# devboard.net
KiCad netlist of a schematic drawn in EAGLE
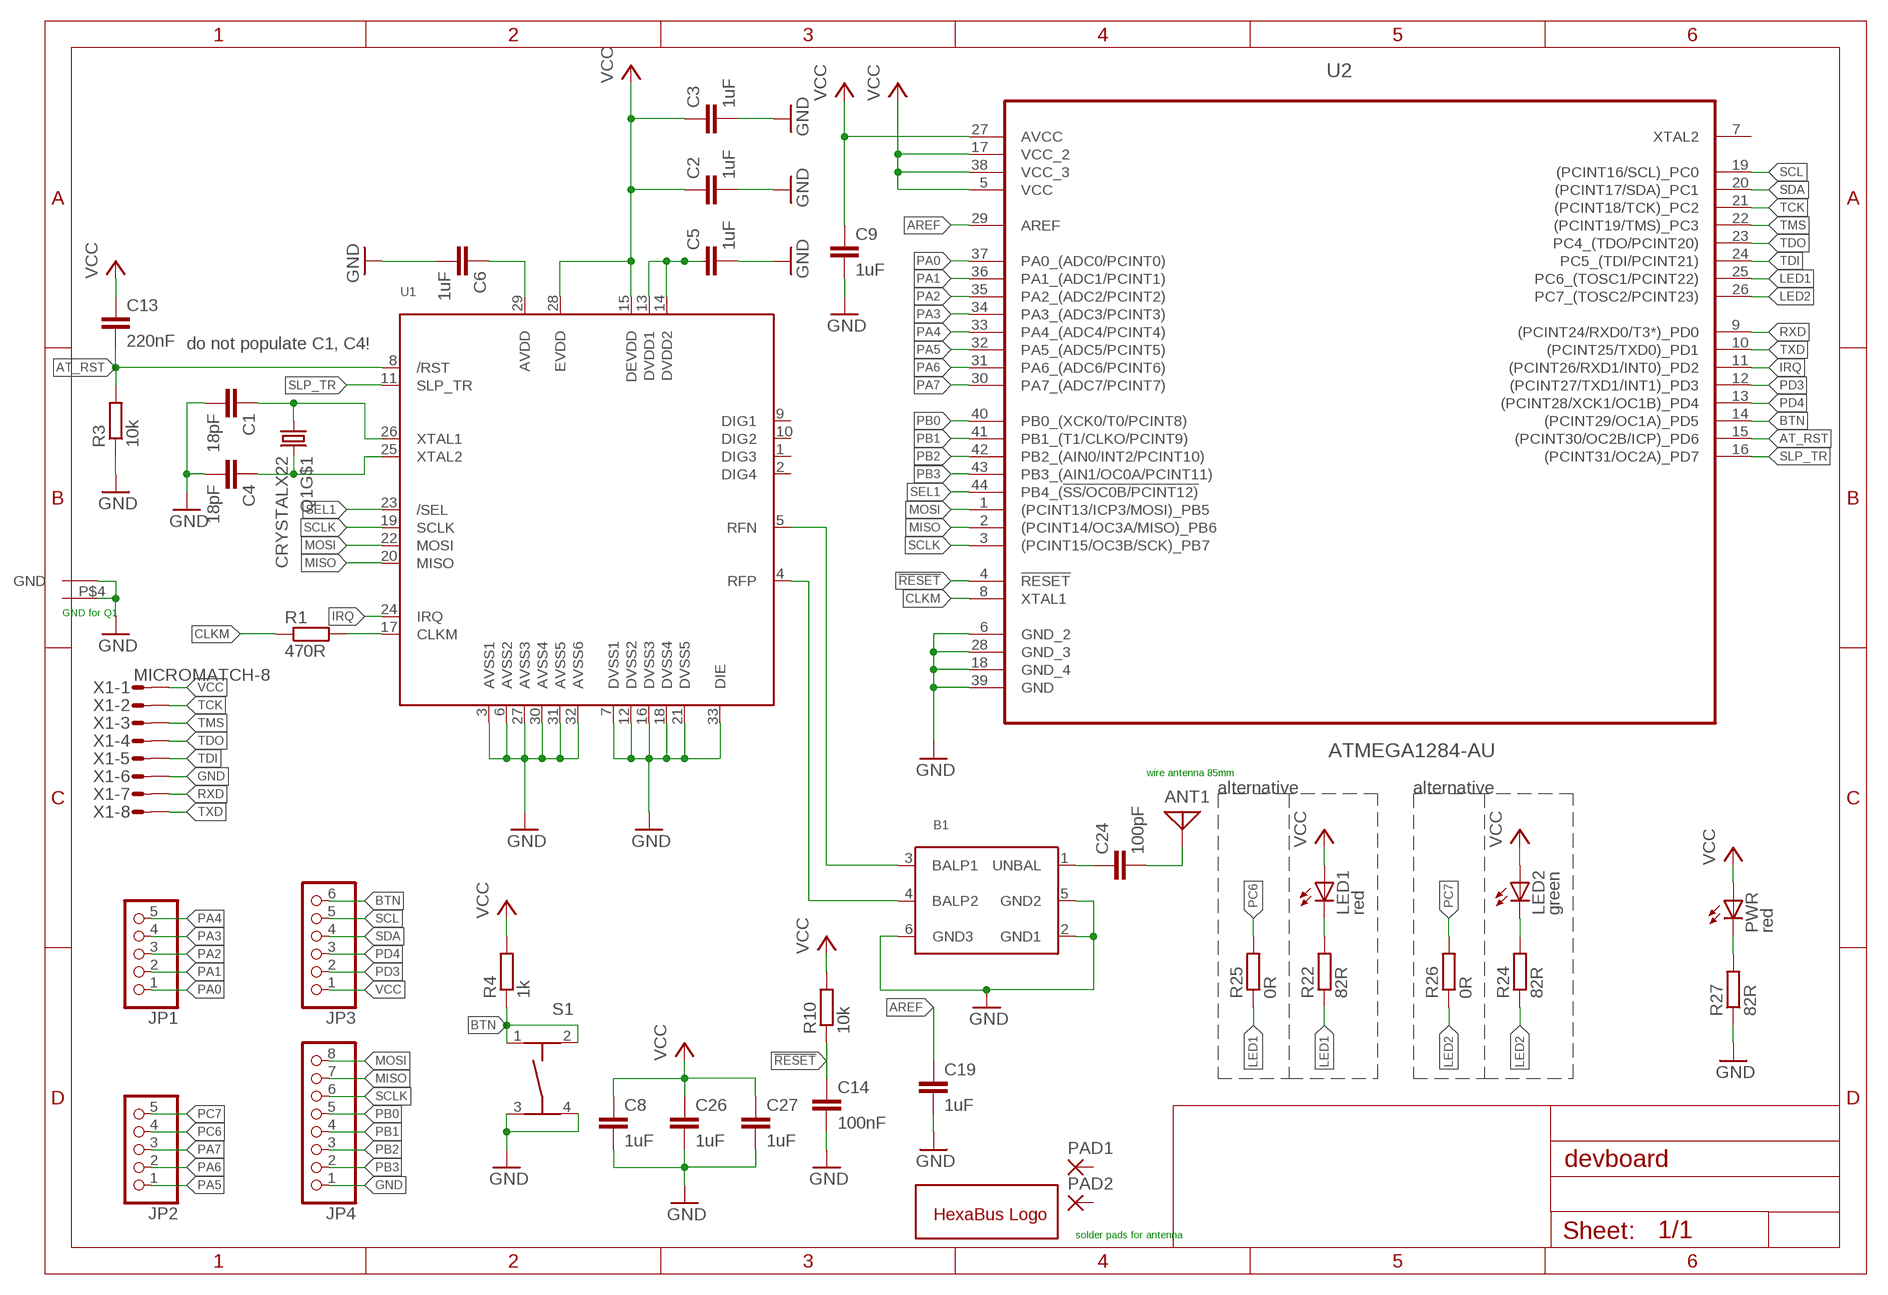
[diagram p0: schematic, sheet 1]

(export (version "E")
  (design (tool "Eeschema 10.0.6"))
  (components
    (comp (ref "ANT1")
      (value "ANTENNA")
      (footprint "eagle-import:PAD-01")
      (libsource (lib "eagle-import") (part "ANTENNA"))
    )
    (comp (ref "B1")
      (value "BALUN+LP")
      (footprint "eagle-import:BALUN0805")
      (libsource (lib "eagle-import") (part "BALUN+LP"))
    )
    (comp (ref "C1")
      (value "18pF")
      (footprint "eagle-import:C0603")
      (libsource (lib "eagle-import") (part "C-EUC0603"))
    )
    (comp (ref "C2")
      (value "1uF")
      (footprint "eagle-import:C0603")
      (libsource (lib "eagle-import") (part "C-EUC0603"))
    )
    (comp (ref "C3")
      (value "1uF")
      (footprint "eagle-import:C0603")
      (libsource (lib "eagle-import") (part "C-EUC0603"))
    )
    (comp (ref "C4")
      (value "18pF")
      (footprint "eagle-import:C0603")
      (libsource (lib "eagle-import") (part "C-EUC0603"))
    )
    (comp (ref "C5")
      (value "1uF")
      (footprint "eagle-import:C0603")
      (libsource (lib "eagle-import") (part "C-EUC0603"))
    )
    (comp (ref "C6")
      (value "1uF")
      (footprint "eagle-import:C0603")
      (libsource (lib "eagle-import") (part "C-EUC0603"))
    )
    (comp (ref "C8")
      (value "1uF")
      (footprint "eagle-import:C0603")
      (libsource (lib "eagle-import") (part "C-EUC0603"))
    )
    (comp (ref "C9")
      (value "1uF")
      (footprint "eagle-import:C0603")
      (libsource (lib "eagle-import") (part "C-EUC0603"))
    )
    (comp (ref "C13")
      (value "220nF")
      (footprint "eagle-import:C0603")
      (libsource (lib "eagle-import") (part "C-EUC0603"))
    )
    (comp (ref "C14")
      (value "100nF")
      (footprint "eagle-import:C0603")
      (libsource (lib "eagle-import") (part "C-EUC0603"))
    )
    (comp (ref "C19")
      (value "1uF")
      (footprint "eagle-import:C0603")
      (libsource (lib "eagle-import") (part "C-EUC0603"))
    )
    (comp (ref "C24")
      (value "100pF")
      (footprint "eagle-import:C0603")
      (libsource (lib "eagle-import") (part "C-EUC0603"))
    )
    (comp (ref "C26")
      (value "1uF")
      (footprint "eagle-import:C0603")
      (libsource (lib "eagle-import") (part "C-EUC0603"))
    )
    (comp (ref "C27")
      (value "1uF")
      (footprint "eagle-import:C0603")
      (libsource (lib "eagle-import") (part "C-EUC0603"))
    )
    (comp (ref "JP1")
      (value "PINHD-1X5")
      (footprint "eagle-import:1X05")
      (libsource (lib "eagle-import") (part "PINHD-1X5"))
    )
    (comp (ref "JP2")
      (value "PINHD-1X5")
      (footprint "eagle-import:1X05")
      (libsource (lib "eagle-import") (part "PINHD-1X5"))
    )
    (comp (ref "JP3")
      (value "PINHD-1X6")
      (footprint "eagle-import:1X06")
      (libsource (lib "eagle-import") (part "PINHD-1X6"))
    )
    (comp (ref "JP4")
      (value "PINHD-1X8")
      (footprint "eagle-import:1X08")
      (libsource (lib "eagle-import") (part "PINHD-1X8"))
    )
    (comp (ref "LED1")
      (value "red")
      (footprint "eagle-import:CHIP-LED0603")
      (libsource (lib "eagle-import") (part "LEDCHIP-LED0603"))
    )
    (comp (ref "LED2")
      (value "green")
      (footprint "eagle-import:CHIP-LED0603")
      (libsource (lib "eagle-import") (part "LEDCHIP-LED0603"))
    )
    (comp (ref "PAD1")
      (value "SMD2")
      (footprint "eagle-import:SMD1,27-2,54")
      (libsource (lib "eagle-import") (part "SMD2"))
    )
    (comp (ref "PAD2")
      (value "SMD2")
      (footprint "eagle-import:SMD1,27-2,54")
      (libsource (lib "eagle-import") (part "SMD2"))
    )
    (comp (ref "PWR")
      (value "red")
      (footprint "eagle-import:CHIP-LED0603")
      (libsource (lib "eagle-import") (part "LEDCHIP-LED0603"))
    )
    (comp (ref "Q1")
      (value "CRYSTALX22")
      (footprint "eagle-import:X22")
      (libsource (lib "eagle-import") (part "CRYSTALX22"))
    )
    (comp (ref "R1")
      (value "470R")
      (footprint "eagle-import:R0603")
      (libsource (lib "eagle-import") (part "R-EU_R0603"))
    )
    (comp (ref "R3")
      (value "10k")
      (footprint "eagle-import:R0603")
      (libsource (lib "eagle-import") (part "R-EU_R0603"))
    )
    (comp (ref "R4")
      (value "1k")
      (footprint "eagle-import:R0603")
      (libsource (lib "eagle-import") (part "R-EU_R0603"))
    )
    (comp (ref "R10")
      (value "10k")
      (footprint "eagle-import:R0603")
      (libsource (lib "eagle-import") (part "R-EU_R0603"))
    )
    (comp (ref "R22")
      (value "82R")
      (footprint "eagle-import:R0603")
      (libsource (lib "eagle-import") (part "R-EU_R0603"))
    )
    (comp (ref "R24")
      (value "82R")
      (footprint "eagle-import:R0603")
      (libsource (lib "eagle-import") (part "R-EU_R0603"))
    )
    (comp (ref "R25")
      (value "0R")
      (footprint "eagle-import:R0603")
      (libsource (lib "eagle-import") (part "R-EU_R0603"))
    )
    (comp (ref "R26")
      (value "0R")
      (footprint "eagle-import:R0603")
      (libsource (lib "eagle-import") (part "R-EU_R0603"))
    )
    (comp (ref "R27")
      (value "82R")
      (footprint "eagle-import:R0603")
      (libsource (lib "eagle-import") (part "R-EU_R0603"))
    )
    (comp (ref "S1")
      (value "TASTER-9314_SMD")
      (footprint "eagle-import:TASTER-9314_SMD")
      (libsource (lib "eagle-import") (part "TASTER-9314_SMD"))
    )
    (comp (ref "U$1")
      (value "HEXAKRAKE")
      (footprint "eagle-import:HEXAKRAKE")
      (libsource (lib "eagle-import") (part "HEXAKRAKE"))
    )
    (comp (ref "U1")
      (value "AT86RF212")
      (footprint "eagle-import:32QN2")
      (libsource (lib "eagle-import") (part "AT86RF212"))
    )
    (comp (ref "U2")
      (value "ATMEGA1284-AU")
      (footprint "eagle-import:QFP80P1200X1200X120-44N")
      (libsource (lib "eagle-import") (part "ATMEGA1284-AU"))
    )
    (comp (ref "X1")
      (value "MICROMATCH-8")
      (footprint "eagle-import:MICROMATCH-8")
      (fields (field (name "MF") "FARNELL") (field (name "MPN") "7-215464-8"))
      (libsource (lib "eagle-import") (part "MICROMATCH-8"))
    )
  )
  (nets
    (net (code "1") (name "/~{RESET}") (class "Default")
      (node (ref "C14") (pin "1") (pinfunction "1_1") (pintype "passive"))
      (node (ref "R10") (pin "1") (pinfunction "1_1") (pintype "passive"))
      (node (ref "U2") (pin "4") (pinfunction "~{RESET}_4") (pintype "input"))
    )
    (net (code "2") (name "AREF") (class "Default")
      (node (ref "C19") (pin "1") (pinfunction "1_1") (pintype "passive"))
      (node (ref "U2") (pin "29") (pinfunction "AREF_29") (pintype "passive"))
    )
    (net (code "3") (name "AT_RST") (class "Default")
      (node (ref "C13") (pin "2") (pinfunction "2_2") (pintype "passive"))
      (node (ref "R3") (pin "2") (pinfunction "2_2") (pintype "passive"))
      (node (ref "U1") (pin "8") (pinfunction "/RST_8") (pintype "bidirectional"))
      (node (ref "U2") (pin "15") (pinfunction "(PCINT30/OC2B/ICP)_PD6_15") (pintype "bidirectional"))
    )
    (net (code "4") (name "BTN") (class "Default")
      (node (ref "JP3") (pin "6") (pinfunction "6_6") (pintype "passive"))
      (node (ref "R4") (pin "1") (pinfunction "1_1") (pintype "passive"))
      (node (ref "S1") (pin "1") (pinfunction "1_1") (pintype "passive"))
      (node (ref "S1") (pin "2") (pinfunction "2_2") (pintype "passive"))
      (node (ref "U2") (pin "14") (pinfunction "(PCINT29/OC1A)_PD5_14") (pintype "bidirectional"))
    )
    (net (code "5") (name "CLKM") (class "Default")
      (node (ref "R1") (pin "1") (pinfunction "1_1") (pintype "passive"))
      (node (ref "U2") (pin "8") (pinfunction "XTAL1_8") (pintype "input"))
    )
    (net (code "6") (name "GND") (class "Default")
      (node (ref "B1") (pin "2") (pinfunction "GND1_2") (pintype "bidirectional"))
      (node (ref "B1") (pin "5") (pinfunction "GND2_5") (pintype "bidirectional"))
      (node (ref "B1") (pin "6") (pinfunction "GND3_6") (pintype "bidirectional"))
      (node (ref "C1") (pin "2") (pinfunction "2_2") (pintype "passive"))
      (node (ref "C14") (pin "2") (pinfunction "2_2") (pintype "passive"))
      (node (ref "C19") (pin "2") (pinfunction "2_2") (pintype "passive"))
      (node (ref "C2") (pin "2") (pinfunction "2_2") (pintype "passive"))
      (node (ref "C26") (pin "2") (pinfunction "2_2") (pintype "passive"))
      (node (ref "C27") (pin "2") (pinfunction "2_2") (pintype "passive"))
      (node (ref "C3") (pin "2") (pinfunction "2_2") (pintype "passive"))
      (node (ref "C4") (pin "2") (pinfunction "2_2") (pintype "passive"))
      (node (ref "C5") (pin "2") (pinfunction "2_2") (pintype "passive"))
      (node (ref "C6") (pin "2") (pinfunction "2_2") (pintype "passive"))
      (node (ref "C8") (pin "2") (pinfunction "2_2") (pintype "passive"))
      (node (ref "C9") (pin "2") (pinfunction "2_2") (pintype "passive"))
      (node (ref "JP4") (pin "1") (pinfunction "1_1") (pintype "passive"))
      (node (ref "Q1") (pin "P$2") (pinfunction "GND_P$2") (pintype "bidirectional"))
      (node (ref "Q1") (pin "P$4") (pinfunction "GND1_P$4") (pintype "bidirectional"))
      (node (ref "R27") (pin "1") (pinfunction "1_1") (pintype "passive"))
      (node (ref "R3") (pin "1") (pinfunction "1_1") (pintype "passive"))
      (node (ref "S1") (pin "3") (pinfunction "3_3") (pintype "passive"))
      (node (ref "S1") (pin "4") (pinfunction "4_4") (pintype "passive"))
      (node (ref "U1") (pin "12") (pinfunction "DVSS2_12") (pintype "bidirectional"))
      (node (ref "U1") (pin "16") (pinfunction "DVSS3_16") (pintype "bidirectional"))
      (node (ref "U1") (pin "18") (pinfunction "DVSS4_18") (pintype "bidirectional"))
      (node (ref "U1") (pin "21") (pinfunction "DVSS5_21") (pintype "bidirectional"))
      (node (ref "U1") (pin "27") (pinfunction "AVSS3_27") (pintype "bidirectional"))
      (node (ref "U1") (pin "3") (pinfunction "AVSS1_3") (pintype "bidirectional"))
      (node (ref "U1") (pin "30") (pinfunction "AVSS4_30") (pintype "bidirectional"))
      (node (ref "U1") (pin "31") (pinfunction "AVSS5_31") (pintype "bidirectional"))
      (node (ref "U1") (pin "32") (pinfunction "AVSS6_32") (pintype "bidirectional"))
      (node (ref "U1") (pin "33") (pinfunction "DIE_33") (pintype "bidirectional"))
      (node (ref "U1") (pin "6") (pinfunction "AVSS2_6") (pintype "bidirectional"))
      (node (ref "U1") (pin "7") (pinfunction "DVSS1_7") (pintype "bidirectional"))
      (node (ref "U2") (pin "18") (pinfunction "GND_4_18") (pintype "passive"))
      (node (ref "U2") (pin "28") (pinfunction "GND_3_28") (pintype "passive"))
      (node (ref "U2") (pin "39") (pinfunction "GND_39") (pintype "passive"))
      (node (ref "U2") (pin "6") (pinfunction "GND_2_6") (pintype "passive"))
      (node (ref "X1") (pin "6") (pinfunction "S_6") (pintype "passive"))
    )
    (net (code "7") (name "IRQ") (class "Default")
      (node (ref "U1") (pin "24") (pinfunction "IRQ_24") (pintype "bidirectional"))
      (node (ref "U2") (pin "11") (pinfunction "(PCINT26/RXD1/INT0)_PD2_11") (pintype "bidirectional"))
    )
    (net (code "8") (name "LED1") (class "Default")
      (node (ref "R22") (pin "1") (pinfunction "1_1") (pintype "passive"))
      (node (ref "R25") (pin "1") (pinfunction "1_1") (pintype "passive"))
      (node (ref "U2") (pin "25") (pinfunction "PC6_(TOSC1/PCINT22)_25") (pintype "bidirectional"))
    )
    (net (code "9") (name "LED2") (class "Default")
      (node (ref "R24") (pin "1") (pinfunction "1_1") (pintype "passive"))
      (node (ref "R26") (pin "1") (pinfunction "1_1") (pintype "passive"))
      (node (ref "U2") (pin "26") (pinfunction "PC7_(TOSC2/PCINT23)_26") (pintype "bidirectional"))
    )
    (net (code "10") (name "MISO") (class "Default")
      (node (ref "JP4") (pin "7") (pinfunction "7_7") (pintype "passive"))
      (node (ref "U1") (pin "20") (pinfunction "MISO_20") (pintype "bidirectional"))
      (node (ref "U2") (pin "2") (pinfunction "(PCINT14/OC3A/MISO)_PB6_2") (pintype "bidirectional"))
    )
    (net (code "11") (name "MOSI") (class "Default")
      (node (ref "JP4") (pin "8") (pinfunction "8_8") (pintype "passive"))
      (node (ref "U1") (pin "22") (pinfunction "MOSI_22") (pintype "bidirectional"))
      (node (ref "U2") (pin "1") (pinfunction "(PCINT13/ICP3/MOSI)_PB5_1") (pintype "bidirectional"))
    )
    (net (code "12") (name "Net-(ANT1-Pad1)") (class "Default")
      (node (ref "ANT1") (pin "1") (pinfunction "1_1") (pintype "output"))
      (node (ref "C24") (pin "2") (pinfunction "2_2") (pintype "passive"))
    )
    (net (code "13") (name "Net-(B1-BALP1)") (class "Default")
      (node (ref "B1") (pin "3") (pinfunction "BALP1_3") (pintype "bidirectional"))
      (node (ref "U1") (pin "5") (pinfunction "RFN_5") (pintype "bidirectional"))
    )
    (net (code "14") (name "Net-(B1-BALP2)") (class "Default")
      (node (ref "B1") (pin "4") (pinfunction "BALP2_4") (pintype "bidirectional"))
      (node (ref "U1") (pin "4") (pinfunction "RFP_4") (pintype "bidirectional"))
    )
    (net (code "15") (name "Net-(B1-UNBAL)") (class "Default")
      (node (ref "B1") (pin "1") (pinfunction "UNBAL_1") (pintype "bidirectional"))
      (node (ref "C24") (pin "1") (pinfunction "1_1") (pintype "passive"))
    )
    (net (code "16") (name "Net-(LED1-PadC)") (class "Default")
      (node (ref "LED1") (pin "C") (pinfunction "C_C") (pintype "passive"))
      (node (ref "R22") (pin "2") (pinfunction "2_2") (pintype "passive"))
    )
    (net (code "17") (name "Net-(LED2-PadC)") (class "Default")
      (node (ref "LED2") (pin "C") (pinfunction "C_C") (pintype "passive"))
      (node (ref "R24") (pin "2") (pinfunction "2_2") (pintype "passive"))
    )
    (net (code "18") (name "Net-(PWR-PadC)") (class "Default")
      (node (ref "PWR") (pin "C") (pinfunction "C_C") (pintype "passive"))
      (node (ref "R27") (pin "2") (pinfunction "2_2") (pintype "passive"))
    )
    (net (code "19") (name "Net-(Q1A-1)") (class "Default")
      (node (ref "C1") (pin "1") (pinfunction "1_1") (pintype "passive"))
      (node (ref "Q1") (pin "P$1") (pinfunction "1_P$1") (pintype "passive"))
      (node (ref "U1") (pin "26") (pinfunction "XTAL1_26") (pintype "bidirectional"))
    )
    (net (code "20") (name "Net-(Q1A-2)") (class "Default")
      (node (ref "C4") (pin "1") (pinfunction "1_1") (pintype "passive"))
      (node (ref "Q1") (pin "P$3") (pinfunction "2_P$3") (pintype "passive"))
      (node (ref "U1") (pin "25") (pinfunction "XTAL2_25") (pintype "bidirectional"))
    )
    (net (code "21") (name "Net-(U1-AVDD)") (class "Default")
      (node (ref "C6") (pin "1") (pinfunction "1_1") (pintype "passive"))
      (node (ref "U1") (pin "29") (pinfunction "AVDD_29") (pintype "bidirectional"))
    )
    (net (code "22") (name "Net-(U1-CLKM)") (class "Default")
      (node (ref "R1") (pin "2") (pinfunction "2_2") (pintype "passive"))
      (node (ref "U1") (pin "17") (pinfunction "CLKM_17") (pintype "bidirectional"))
    )
    (net (code "23") (name "Net-(U1-DVDD1)") (class "Default")
      (node (ref "C5") (pin "1") (pinfunction "1_1") (pintype "passive"))
      (node (ref "U1") (pin "13") (pinfunction "DVDD1_13") (pintype "bidirectional"))
      (node (ref "U1") (pin "14") (pinfunction "DVDD2_14") (pintype "bidirectional"))
    )
    (net (code "24") (name "PA0") (class "Default")
      (node (ref "JP1") (pin "1") (pinfunction "1_1") (pintype "passive"))
      (node (ref "U2") (pin "37") (pinfunction "PA0_(ADC0/PCINT0)_37") (pintype "bidirectional"))
    )
    (net (code "25") (name "PA1") (class "Default")
      (node (ref "JP1") (pin "2") (pinfunction "2_2") (pintype "passive"))
      (node (ref "U2") (pin "36") (pinfunction "PA1_(ADC1/PCINT1)_36") (pintype "bidirectional"))
    )
    (net (code "26") (name "PA2") (class "Default")
      (node (ref "JP1") (pin "3") (pinfunction "3_3") (pintype "passive"))
      (node (ref "U2") (pin "35") (pinfunction "PA2_(ADC2/PCINT2)_35") (pintype "bidirectional"))
    )
    (net (code "27") (name "PA3") (class "Default")
      (node (ref "JP1") (pin "4") (pinfunction "4_4") (pintype "passive"))
      (node (ref "U2") (pin "34") (pinfunction "PA3_(ADC3/PCINT3)_34") (pintype "bidirectional"))
    )
    (net (code "28") (name "PA4") (class "Default")
      (node (ref "JP1") (pin "5") (pinfunction "5_5") (pintype "passive"))
      (node (ref "U2") (pin "33") (pinfunction "PA4_(ADC4/PCINT4)_33") (pintype "bidirectional"))
    )
    (net (code "29") (name "PA5") (class "Default")
      (node (ref "JP2") (pin "1") (pinfunction "1_1") (pintype "passive"))
      (node (ref "U2") (pin "32") (pinfunction "PA5_(ADC5/PCINT5)_32") (pintype "bidirectional"))
    )
    (net (code "30") (name "PA6") (class "Default")
      (node (ref "JP2") (pin "2") (pinfunction "2_2") (pintype "passive"))
      (node (ref "U2") (pin "31") (pinfunction "PA6_(ADC6/PCINT6)_31") (pintype "bidirectional"))
    )
    (net (code "31") (name "PA7") (class "Default")
      (node (ref "JP2") (pin "3") (pinfunction "3_3") (pintype "passive"))
      (node (ref "U2") (pin "30") (pinfunction "PA7_(ADC7/PCINT7)_30") (pintype "bidirectional"))
    )
    (net (code "32") (name "PB0") (class "Default")
      (node (ref "JP4") (pin "5") (pinfunction "5_5") (pintype "passive"))
      (node (ref "U2") (pin "40") (pinfunction "PB0_(XCK0/T0/PCINT8)_40") (pintype "bidirectional"))
    )
    (net (code "33") (name "PB1") (class "Default")
      (node (ref "JP4") (pin "4") (pinfunction "4_4") (pintype "passive"))
      (node (ref "U2") (pin "41") (pinfunction "PB1_(T1/CLKO/PCINT9)_41") (pintype "bidirectional"))
    )
    (net (code "34") (name "PB2") (class "Default")
      (node (ref "JP4") (pin "3") (pinfunction "3_3") (pintype "passive"))
      (node (ref "U2") (pin "42") (pinfunction "PB2_(AIN0/INT2/PCINT10)_42") (pintype "bidirectional"))
    )
    (net (code "35") (name "PB3") (class "Default")
      (node (ref "JP4") (pin "2") (pinfunction "2_2") (pintype "passive"))
      (node (ref "U2") (pin "43") (pinfunction "PB3_(AIN1/OC0A/PCINT11)_43") (pintype "bidirectional"))
    )
    (net (code "36") (name "PC6") (class "Default")
      (node (ref "JP2") (pin "4") (pinfunction "4_4") (pintype "passive"))
      (node (ref "R25") (pin "2") (pinfunction "2_2") (pintype "passive"))
    )
    (net (code "37") (name "PC7") (class "Default")
      (node (ref "JP2") (pin "5") (pinfunction "5_5") (pintype "passive"))
      (node (ref "R26") (pin "2") (pinfunction "2_2") (pintype "passive"))
    )
    (net (code "38") (name "PD3") (class "Default")
      (node (ref "JP3") (pin "2") (pinfunction "2_2") (pintype "passive"))
      (node (ref "U2") (pin "12") (pinfunction "(PCINT27/TXD1/INT1)_PD3_12") (pintype "bidirectional"))
    )
    (net (code "39") (name "PD4") (class "Default")
      (node (ref "JP3") (pin "3") (pinfunction "3_3") (pintype "passive"))
      (node (ref "U2") (pin "13") (pinfunction "(PCINT28/XCK1/OC1B)_PD4_13") (pintype "bidirectional"))
    )
    (net (code "40") (name "RXD") (class "Default")
      (node (ref "U2") (pin "9") (pinfunction "(PCINT24/RXD0/T3*)_PD0_9") (pintype "bidirectional"))
      (node (ref "X1") (pin "7") (pinfunction "S_7") (pintype "passive"))
    )
    (net (code "41") (name "SCL") (class "Default")
      (node (ref "JP3") (pin "5") (pinfunction "5_5") (pintype "passive"))
      (node (ref "U2") (pin "19") (pinfunction "(PCINT16/SCL)_PC0_19") (pintype "bidirectional"))
    )
    (net (code "42") (name "SCLK") (class "Default")
      (node (ref "JP4") (pin "6") (pinfunction "6_6") (pintype "passive"))
      (node (ref "U1") (pin "19") (pinfunction "SCLK_19") (pintype "bidirectional"))
      (node (ref "U2") (pin "3") (pinfunction "(PCINT15/OC3B/SCK)_PB7_3") (pintype "bidirectional"))
    )
    (net (code "43") (name "SDA") (class "Default")
      (node (ref "JP3") (pin "4") (pinfunction "4_4") (pintype "passive"))
      (node (ref "U2") (pin "20") (pinfunction "(PCINT17/SDA)_PC1_20") (pintype "bidirectional"))
    )
    (net (code "44") (name "SEL1") (class "Default")
      (node (ref "U1") (pin "23") (pinfunction "/SEL_23") (pintype "bidirectional"))
      (node (ref "U2") (pin "44") (pinfunction "PB4_(~{SS/OC0B/PCINT12})_44") (pintype "bidirectional"))
    )
    (net (code "45") (name "SLP_TR") (class "Default")
      (node (ref "U1") (pin "11") (pinfunction "SLP_TR_11") (pintype "bidirectional"))
      (node (ref "U2") (pin "16") (pinfunction "(PCINT31/OC2A)_PD7_16") (pintype "bidirectional"))
    )
    (net (code "46") (name "TCK") (class "Default")
      (node (ref "U2") (pin "21") (pinfunction "(PCINT18/TCK)_PC2_21") (pintype "bidirectional"))
      (node (ref "X1") (pin "2") (pinfunction "S_2") (pintype "passive"))
    )
    (net (code "47") (name "TDI") (class "Default")
      (node (ref "U2") (pin "24") (pinfunction "PC5_(TDI/PCINT21)_24") (pintype "bidirectional"))
      (node (ref "X1") (pin "5") (pinfunction "S_5") (pintype "passive"))
    )
    (net (code "48") (name "TDO") (class "Default")
      (node (ref "U2") (pin "23") (pinfunction "PC4_(TDO/PCINT20)_23") (pintype "bidirectional"))
      (node (ref "X1") (pin "4") (pinfunction "S_4") (pintype "passive"))
    )
    (net (code "49") (name "TMS") (class "Default")
      (node (ref "U2") (pin "22") (pinfunction "(PCINT19/TMS)_PC3_22") (pintype "bidirectional"))
      (node (ref "X1") (pin "3") (pinfunction "S_3") (pintype "passive"))
    )
    (net (code "50") (name "TXD") (class "Default")
      (node (ref "U2") (pin "10") (pinfunction "(PCINT25/TXD0)_PD1_10") (pintype "bidirectional"))
      (node (ref "X1") (pin "8") (pinfunction "S_8") (pintype "passive"))
    )
    (net (code "51") (name "VCC") (class "Default")
      (node (ref "C13") (pin "1") (pinfunction "1_1") (pintype "passive"))
      (node (ref "C2") (pin "1") (pinfunction "1_1") (pintype "passive"))
      (node (ref "C26") (pin "1") (pinfunction "1_1") (pintype "passive"))
      (node (ref "C27") (pin "1") (pinfunction "1_1") (pintype "passive"))
      (node (ref "C3") (pin "1") (pinfunction "1_1") (pintype "passive"))
      (node (ref "C8") (pin "1") (pinfunction "1_1") (pintype "passive"))
      (node (ref "C9") (pin "1") (pinfunction "1_1") (pintype "passive"))
      (node (ref "JP3") (pin "1") (pinfunction "1_1") (pintype "passive"))
      (node (ref "LED1") (pin "A") (pinfunction "A_A") (pintype "passive"))
      (node (ref "LED2") (pin "A") (pinfunction "A_A") (pintype "passive"))
      (node (ref "PWR") (pin "A") (pinfunction "A_A") (pintype "passive"))
      (node (ref "R10") (pin "2") (pinfunction "2_2") (pintype "passive"))
      (node (ref "R4") (pin "2") (pinfunction "2_2") (pintype "passive"))
      (node (ref "U1") (pin "15") (pinfunction "DEVDD_15") (pintype "bidirectional"))
      (node (ref "U1") (pin "28") (pinfunction "EVDD_28") (pintype "bidirectional"))
      (node (ref "U2") (pin "17") (pinfunction "VCC_2_17") (pintype "power_in"))
      (node (ref "U2") (pin "27") (pinfunction "AVCC_27") (pintype "power_in"))
      (node (ref "U2") (pin "38") (pinfunction "VCC_3_38") (pintype "power_in"))
      (node (ref "U2") (pin "5") (pinfunction "VCC_5") (pintype "power_in"))
      (node (ref "X1") (pin "1") (pinfunction "S_1") (pintype "passive"))
    )
    (net (code "52") (name "unconnected-(PAD1-P-Pad1)") (class "Default")
      (node (ref "PAD1") (pin "1") (pinfunction "P_1") (pintype "passive"))
    )
    (net (code "53") (name "unconnected-(PAD2-P-Pad1)") (class "Default")
      (node (ref "PAD2") (pin "1") (pinfunction "P_1") (pintype "passive"))
    )
    (net (code "54") (name "unconnected-(U1-DIG1-Pad9)") (class "Default")
      (node (ref "U1") (pin "9") (pinfunction "DIG1_9") (pintype "bidirectional"))
    )
    (net (code "55") (name "unconnected-(U1-DIG2-Pad10)") (class "Default")
      (node (ref "U1") (pin "10") (pinfunction "DIG2_10") (pintype "bidirectional"))
    )
    (net (code "56") (name "unconnected-(U1-DIG3-Pad1)") (class "Default")
      (node (ref "U1") (pin "1") (pinfunction "DIG3_1") (pintype "bidirectional"))
    )
    (net (code "57") (name "unconnected-(U1-DIG4-Pad2)") (class "Default")
      (node (ref "U1") (pin "2") (pinfunction "DIG4_2") (pintype "bidirectional"))
    )
    (net (code "58") (name "unconnected-(U2-XTAL2-Pad7)") (class "Default")
      (node (ref "U2") (pin "7") (pinfunction "XTAL2_7") (pintype "output"))
    )
  )
)
